# Atrix_breakout.net
KiCad netlist of a schematic drawn in EAGLE
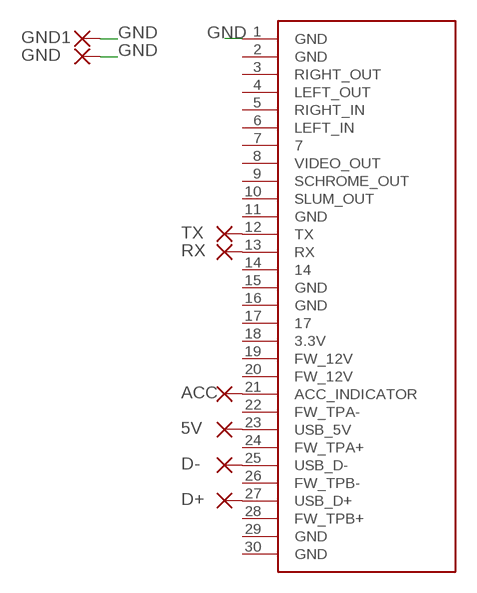
[diagram p0: schematic, sheet 1]

(export (version "E")
  (design (tool "Eeschema 10.0.6"))
  (components
    (comp (ref "5V")
      (value "1,6/0,8")
      (footprint "eagle-import:1,6_0,8")
      (libsource (lib "eagle-import") (part "1,6/0,8"))
    )
    (comp (ref "ACC")
      (value "1,6/0,8")
      (footprint "eagle-import:1,6_0,8")
      (libsource (lib "eagle-import") (part "1,6/0,8"))
    )
    (comp (ref "D+")
      (value "1,6/0,8")
      (footprint "eagle-import:1,6_0,8")
      (libsource (lib "eagle-import") (part "1,6/0,8"))
    )
    (comp (ref "D-")
      (value "1,6/0,8")
      (footprint "eagle-import:1,6_0,8")
      (libsource (lib "eagle-import") (part "1,6/0,8"))
    )
    (comp (ref "GND")
      (value "1,6/0,8")
      (footprint "eagle-import:1,6_0,8")
      (libsource (lib "eagle-import") (part "1,6/0,8"))
    )
    (comp (ref "GND1")
      (value "1,6/0,8")
      (footprint "eagle-import:1,6_0,8")
      (libsource (lib "eagle-import") (part "1,6/0,8"))
    )
    (comp (ref "RX")
      (value "1,6/0,8")
      (footprint "eagle-import:1,6_0,8")
      (libsource (lib "eagle-import") (part "1,6/0,8"))
    )
    (comp (ref "TX")
      (value "1,6/0,8")
      (footprint "eagle-import:1,6_0,8")
      (libsource (lib "eagle-import") (part "1,6/0,8"))
    )
    (comp (ref "U$1")
      (value "IPOD_CONNECTOR_MALE")
      (footprint "eagle-import:IPOD_MALE_CONNECTOR")
      (libsource (lib "eagle-import") (part "IPOD_CONNECTOR_MALE"))
    )
  )
  (nets
    (net (code "1") (name "/GND") (class "Default")
      (node (ref "GND") (pin "1") (pinfunction "P_1") (pintype "passive"))
      (node (ref "GND1") (pin "1") (pinfunction "P_1") (pintype "passive"))
      (node (ref "U$1") (pin "1") (pinfunction "GND_1") (pintype "bidirectional"))
    )
    (net (code "2") (name "Net-(5V-P)") (class "Default")
      (node (ref "5V") (pin "1") (pinfunction "P_1") (pintype "passive"))
      (node (ref "U$1") (pin "23") (pinfunction "USB_5V_23") (pintype "bidirectional"))
    )
    (net (code "3") (name "Net-(ACC-P)") (class "Default")
      (node (ref "ACC") (pin "1") (pinfunction "P_1") (pintype "passive"))
      (node (ref "U$1") (pin "21") (pinfunction "ACC_INDICATOR_21") (pintype "bidirectional"))
    )
    (net (code "4") (name "Net-(D+-P)") (class "Default")
      (node (ref "D+") (pin "1") (pinfunction "P_1") (pintype "passive"))
      (node (ref "U$1") (pin "27") (pinfunction "USB_D+_27") (pintype "bidirectional"))
    )
    (net (code "5") (name "Net-(D--P)") (class "Default")
      (node (ref "D-") (pin "1") (pinfunction "P_1") (pintype "passive"))
      (node (ref "U$1") (pin "25") (pinfunction "USB_D-_25") (pintype "bidirectional"))
    )
    (net (code "6") (name "Net-(RX-P)") (class "Default")
      (node (ref "RX") (pin "1") (pinfunction "P_1") (pintype "passive"))
      (node (ref "U$1") (pin "13") (pinfunction "RX_13") (pintype "bidirectional"))
    )
    (net (code "7") (name "Net-(TX-P)") (class "Default")
      (node (ref "TX") (pin "1") (pinfunction "P_1") (pintype "passive"))
      (node (ref "U$1") (pin "12") (pinfunction "TX_12") (pintype "bidirectional"))
    )
    (net (code "8") (name "unconnected-(U$1-3.3V-Pad18)") (class "Default")
      (node (ref "U$1") (pin "18") (pinfunction "3.3V_18") (pintype "bidirectional"))
    )
    (net (code "9") (name "unconnected-(U$1-FW_12V-Pad19)") (class "Default")
      (node (ref "U$1") (pin "19") (pinfunction "FW_12V_19") (pintype "bidirectional"))
    )
    (net (code "10") (name "unconnected-(U$1-FW_12V-Pad20)") (class "Default")
      (node (ref "U$1") (pin "20") (pinfunction "FW_12V_20") (pintype "bidirectional"))
    )
    (net (code "11") (name "unconnected-(U$1-FW_TPA+-Pad24)") (class "Default")
      (node (ref "U$1") (pin "24") (pinfunction "FW_TPA+_24") (pintype "bidirectional"))
    )
    (net (code "12") (name "unconnected-(U$1-FW_TPA--Pad22)") (class "Default")
      (node (ref "U$1") (pin "22") (pinfunction "FW_TPA-_22") (pintype "bidirectional"))
    )
    (net (code "13") (name "unconnected-(U$1-FW_TPB+-Pad28)") (class "Default")
      (node (ref "U$1") (pin "28") (pinfunction "FW_TPB+_28") (pintype "bidirectional"))
    )
    (net (code "14") (name "unconnected-(U$1-FW_TPB--Pad26)") (class "Default")
      (node (ref "U$1") (pin "26") (pinfunction "FW_TPB-_26") (pintype "bidirectional"))
    )
    (net (code "15") (name "unconnected-(U$1-GND-Pad2)") (class "Default")
      (node (ref "U$1") (pin "2") (pinfunction "GND_2") (pintype "bidirectional"))
    )
    (net (code "16") (name "unconnected-(U$1-GND-Pad11)") (class "Default")
      (node (ref "U$1") (pin "11") (pinfunction "GND_11") (pintype "bidirectional"))
    )
    (net (code "17") (name "unconnected-(U$1-GND-Pad15)") (class "Default")
      (node (ref "U$1") (pin "15") (pinfunction "GND_15") (pintype "bidirectional"))
    )
    (net (code "18") (name "unconnected-(U$1-GND-Pad16)") (class "Default")
      (node (ref "U$1") (pin "16") (pinfunction "GND_16") (pintype "bidirectional"))
    )
    (net (code "19") (name "unconnected-(U$1-GND-Pad29)") (class "Default")
      (node (ref "U$1") (pin "29") (pinfunction "GND_29") (pintype "bidirectional"))
    )
    (net (code "20") (name "unconnected-(U$1-GND-Pad30)") (class "Default")
      (node (ref "U$1") (pin "30") (pinfunction "GND_30") (pintype "bidirectional"))
    )
    (net (code "21") (name "unconnected-(U$1-LEFT_IN-Pad6)") (class "Default")
      (node (ref "U$1") (pin "6") (pinfunction "LEFT_IN_6") (pintype "bidirectional"))
    )
    (net (code "22") (name "unconnected-(U$1-LEFT_OUT-Pad4)") (class "Default")
      (node (ref "U$1") (pin "4") (pinfunction "LEFT_OUT_4") (pintype "bidirectional"))
    )
    (net (code "23") (name "unconnected-(U$1-Pad7)") (class "Default")
      (node (ref "U$1") (pin "7") (pinfunction "7_7") (pintype "bidirectional"))
    )
    (net (code "24") (name "unconnected-(U$1-Pad14)") (class "Default")
      (node (ref "U$1") (pin "14") (pinfunction "14_14") (pintype "bidirectional"))
    )
    (net (code "25") (name "unconnected-(U$1-Pad17)") (class "Default")
      (node (ref "U$1") (pin "17") (pinfunction "17_17") (pintype "bidirectional"))
    )
    (net (code "26") (name "unconnected-(U$1-RIGHT_IN-Pad5)") (class "Default")
      (node (ref "U$1") (pin "5") (pinfunction "RIGHT_IN_5") (pintype "bidirectional"))
    )
    (net (code "27") (name "unconnected-(U$1-RIGHT_OUT-Pad3)") (class "Default")
      (node (ref "U$1") (pin "3") (pinfunction "RIGHT_OUT_3") (pintype "bidirectional"))
    )
    (net (code "28") (name "unconnected-(U$1-SCHROME_OUT-Pad9)") (class "Default")
      (node (ref "U$1") (pin "9") (pinfunction "SCHROME_OUT_9") (pintype "bidirectional"))
    )
    (net (code "29") (name "unconnected-(U$1-SLUM_OUT-Pad10)") (class "Default")
      (node (ref "U$1") (pin "10") (pinfunction "SLUM_OUT_10") (pintype "bidirectional"))
    )
    (net (code "30") (name "unconnected-(U$1-VIDEO_OUT-Pad8)") (class "Default")
      (node (ref "U$1") (pin "8") (pinfunction "VIDEO_OUT_8") (pintype "bidirectional"))
    )
  )
)
